# TheLittleEngineers_org-27C512E-TO-2532S-.net
KiCad netlist of a schematic drawn in EAGLE
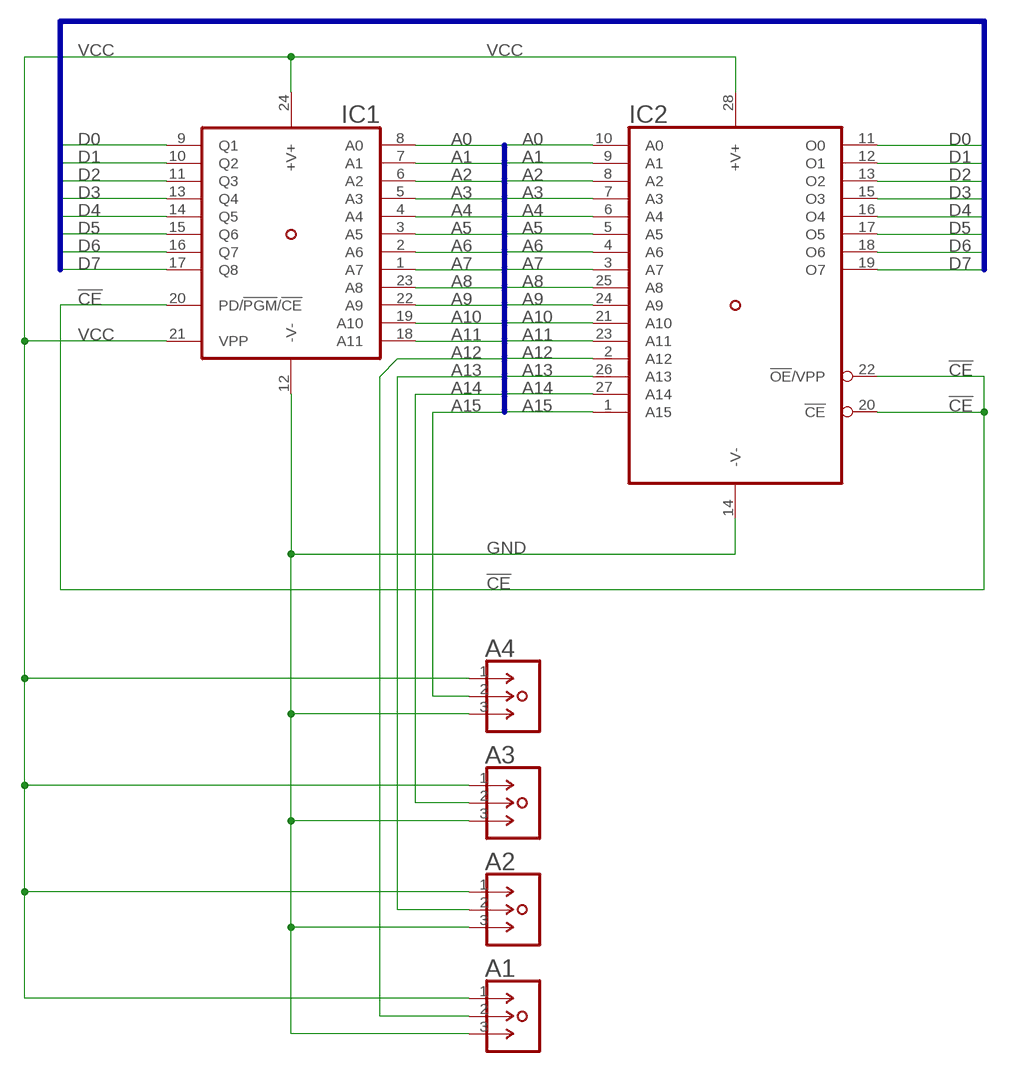
[diagram p0: schematic, sheet 1]

(export (version "E")
  (design (tool "Eeschema 10.0.6"))
  (components
    (comp (ref "A1")
      (value "1X03-STAGGERED-S")
      (footprint "eagle-import:1X03-STAGGERED")
      (libsource (lib "eagle-import") (part "1X03-STAGGERED-S"))
    )
    (comp (ref "A2")
      (value "1X03-STAGGERED-S")
      (footprint "eagle-import:1X03-STAGGERED")
      (libsource (lib "eagle-import") (part "1X03-STAGGERED-S"))
    )
    (comp (ref "A3")
      (value "1X03-STAGGERED-S")
      (footprint "eagle-import:1X03-STAGGERED")
      (libsource (lib "eagle-import") (part "1X03-STAGGERED-S"))
    )
    (comp (ref "A4")
      (value "1X03-STAGGERED-S")
      (footprint "eagle-import:1X03-STAGGERED")
      (libsource (lib "eagle-import") (part "1X03-STAGGERED-S"))
    )
    (comp (ref "IC1")
      (value "TMS2532-NO")
      (footprint "eagle-import:DIL24-6-NO-OUTLINE")
      (libsource (lib "eagle-import") (part "TMS2532-NO"))
    )
    (comp (ref "IC2")
      (value "27C512D-NO")
      (footprint "eagle-import:DIL28-6-NO-OUTLINE")
      (libsource (lib "eagle-import") (part "27C512D-NO"))
    )
  )
  (nets
    (net (code "1") (name "/A0") (class "Default")
      (node (ref "IC1") (pin "8") (pinfunction "A0_8") (pintype "input"))
      (node (ref "IC2") (pin "10") (pinfunction "A0_10") (pintype "input"))
    )
    (net (code "2") (name "/A1") (class "Default")
      (node (ref "IC1") (pin "7") (pinfunction "A1_7") (pintype "input"))
      (node (ref "IC2") (pin "9") (pinfunction "A1_9") (pintype "input"))
    )
    (net (code "3") (name "/A2") (class "Default")
      (node (ref "IC1") (pin "6") (pinfunction "A2_6") (pintype "input"))
      (node (ref "IC2") (pin "8") (pinfunction "A2_8") (pintype "input"))
    )
    (net (code "4") (name "/A3") (class "Default")
      (node (ref "IC1") (pin "5") (pinfunction "A3_5") (pintype "input"))
      (node (ref "IC2") (pin "7") (pinfunction "A3_7") (pintype "input"))
    )
    (net (code "5") (name "/A4") (class "Default")
      (node (ref "IC1") (pin "4") (pinfunction "A4_4") (pintype "input"))
      (node (ref "IC2") (pin "6") (pinfunction "A4_6") (pintype "input"))
    )
    (net (code "6") (name "/A5") (class "Default")
      (node (ref "IC1") (pin "3") (pinfunction "A5_3") (pintype "input"))
      (node (ref "IC2") (pin "5") (pinfunction "A5_5") (pintype "input"))
    )
    (net (code "7") (name "/A6") (class "Default")
      (node (ref "IC1") (pin "2") (pinfunction "A6_2") (pintype "input"))
      (node (ref "IC2") (pin "4") (pinfunction "A6_4") (pintype "input"))
    )
    (net (code "8") (name "/A7") (class "Default")
      (node (ref "IC1") (pin "1") (pinfunction "A7_1") (pintype "input"))
      (node (ref "IC2") (pin "3") (pinfunction "A7_3") (pintype "input"))
    )
    (net (code "9") (name "/A8") (class "Default")
      (node (ref "IC1") (pin "23") (pinfunction "A8_23") (pintype "input"))
      (node (ref "IC2") (pin "25") (pinfunction "A8_25") (pintype "input"))
    )
    (net (code "10") (name "/A9") (class "Default")
      (node (ref "IC1") (pin "22") (pinfunction "A9_22") (pintype "input"))
      (node (ref "IC2") (pin "24") (pinfunction "A9_24") (pintype "input"))
    )
    (net (code "11") (name "/A10") (class "Default")
      (node (ref "IC1") (pin "19") (pinfunction "A10_19") (pintype "input"))
      (node (ref "IC2") (pin "21") (pinfunction "A10_21") (pintype "input"))
    )
    (net (code "12") (name "/A11") (class "Default")
      (node (ref "IC1") (pin "18") (pinfunction "A11_18") (pintype "input"))
      (node (ref "IC2") (pin "23") (pinfunction "A11_23") (pintype "input"))
    )
    (net (code "13") (name "/A12") (class "Default")
      (node (ref "A1") (pin "2") (pinfunction "2_2") (pintype "passive"))
      (node (ref "IC2") (pin "2") (pinfunction "A12_2") (pintype "input"))
    )
    (net (code "14") (name "/A13") (class "Default")
      (node (ref "A2") (pin "2") (pinfunction "2_2") (pintype "passive"))
      (node (ref "IC2") (pin "26") (pinfunction "A13_26") (pintype "input"))
    )
    (net (code "15") (name "/A14") (class "Default")
      (node (ref "A3") (pin "2") (pinfunction "2_2") (pintype "passive"))
      (node (ref "IC2") (pin "27") (pinfunction "A14_27") (pintype "input"))
    )
    (net (code "16") (name "/A15") (class "Default")
      (node (ref "A4") (pin "2") (pinfunction "2_2") (pintype "passive"))
      (node (ref "IC2") (pin "1") (pinfunction "A15_1") (pintype "input"))
    )
    (net (code "17") (name "/D0") (class "Default")
      (node (ref "IC1") (pin "9") (pinfunction "Q1_9") (pintype "tri_state"))
      (node (ref "IC2") (pin "11") (pinfunction "O0_11") (pintype "tri_state"))
    )
    (net (code "18") (name "/D1") (class "Default")
      (node (ref "IC1") (pin "10") (pinfunction "Q2_10") (pintype "tri_state"))
      (node (ref "IC2") (pin "12") (pinfunction "O1_12") (pintype "tri_state"))
    )
    (net (code "19") (name "/D2") (class "Default")
      (node (ref "IC1") (pin "11") (pinfunction "Q3_11") (pintype "tri_state"))
      (node (ref "IC2") (pin "13") (pinfunction "O2_13") (pintype "tri_state"))
    )
    (net (code "20") (name "/D3") (class "Default")
      (node (ref "IC1") (pin "13") (pinfunction "Q4_13") (pintype "tri_state"))
      (node (ref "IC2") (pin "15") (pinfunction "O3_15") (pintype "tri_state"))
    )
    (net (code "21") (name "/D4") (class "Default")
      (node (ref "IC1") (pin "14") (pinfunction "Q5_14") (pintype "tri_state"))
      (node (ref "IC2") (pin "16") (pinfunction "O4_16") (pintype "tri_state"))
    )
    (net (code "22") (name "/D5") (class "Default")
      (node (ref "IC1") (pin "15") (pinfunction "Q6_15") (pintype "tri_state"))
      (node (ref "IC2") (pin "17") (pinfunction "O5_17") (pintype "tri_state"))
    )
    (net (code "23") (name "/D6") (class "Default")
      (node (ref "IC1") (pin "16") (pinfunction "Q7_16") (pintype "tri_state"))
      (node (ref "IC2") (pin "18") (pinfunction "O6_18") (pintype "tri_state"))
    )
    (net (code "24") (name "/D7") (class "Default")
      (node (ref "IC1") (pin "17") (pinfunction "Q8_17") (pintype "tri_state"))
      (node (ref "IC2") (pin "19") (pinfunction "O7_19") (pintype "tri_state"))
    )
    (net (code "25") (name "/GND") (class "Default")
      (node (ref "A1") (pin "3") (pinfunction "3_3") (pintype "passive"))
      (node (ref "A2") (pin "3") (pinfunction "3_3") (pintype "passive"))
      (node (ref "A3") (pin "3") (pinfunction "3_3") (pintype "passive"))
      (node (ref "A4") (pin "3") (pinfunction "3_3") (pintype "passive"))
      (node (ref "IC1") (pin "12") (pinfunction "-V-_12") (pintype "power_in"))
      (node (ref "IC2") (pin "14") (pinfunction "-V-_14") (pintype "power_in"))
    )
    (net (code "26") (name "/VCC") (class "Default")
      (node (ref "A1") (pin "1") (pinfunction "1_1") (pintype "passive"))
      (node (ref "A2") (pin "1") (pinfunction "1_1") (pintype "passive"))
      (node (ref "A3") (pin "1") (pinfunction "1_1") (pintype "passive"))
      (node (ref "A4") (pin "1") (pinfunction "1_1") (pintype "passive"))
      (node (ref "IC1") (pin "21") (pinfunction "VPP_21") (pintype "input"))
      (node (ref "IC1") (pin "24") (pinfunction "+V+_24") (pintype "power_in"))
      (node (ref "IC2") (pin "28") (pinfunction "+V+_28") (pintype "power_in"))
    )
    (net (code "27") (name "/~{CE}") (class "Default")
      (node (ref "IC1") (pin "20") (pinfunction "PD/~{PGM}/~{CE}_20") (pintype "input"))
      (node (ref "IC2") (pin "20") (pinfunction "~{CE}_20") (pintype "input"))
      (node (ref "IC2") (pin "22") (pinfunction "~{OE}/VPP_22") (pintype "input"))
    )
  )
)
